# bitTree_2024-10-30.net
KiCad netlist of a schematic drawn in EasyEDA Pro
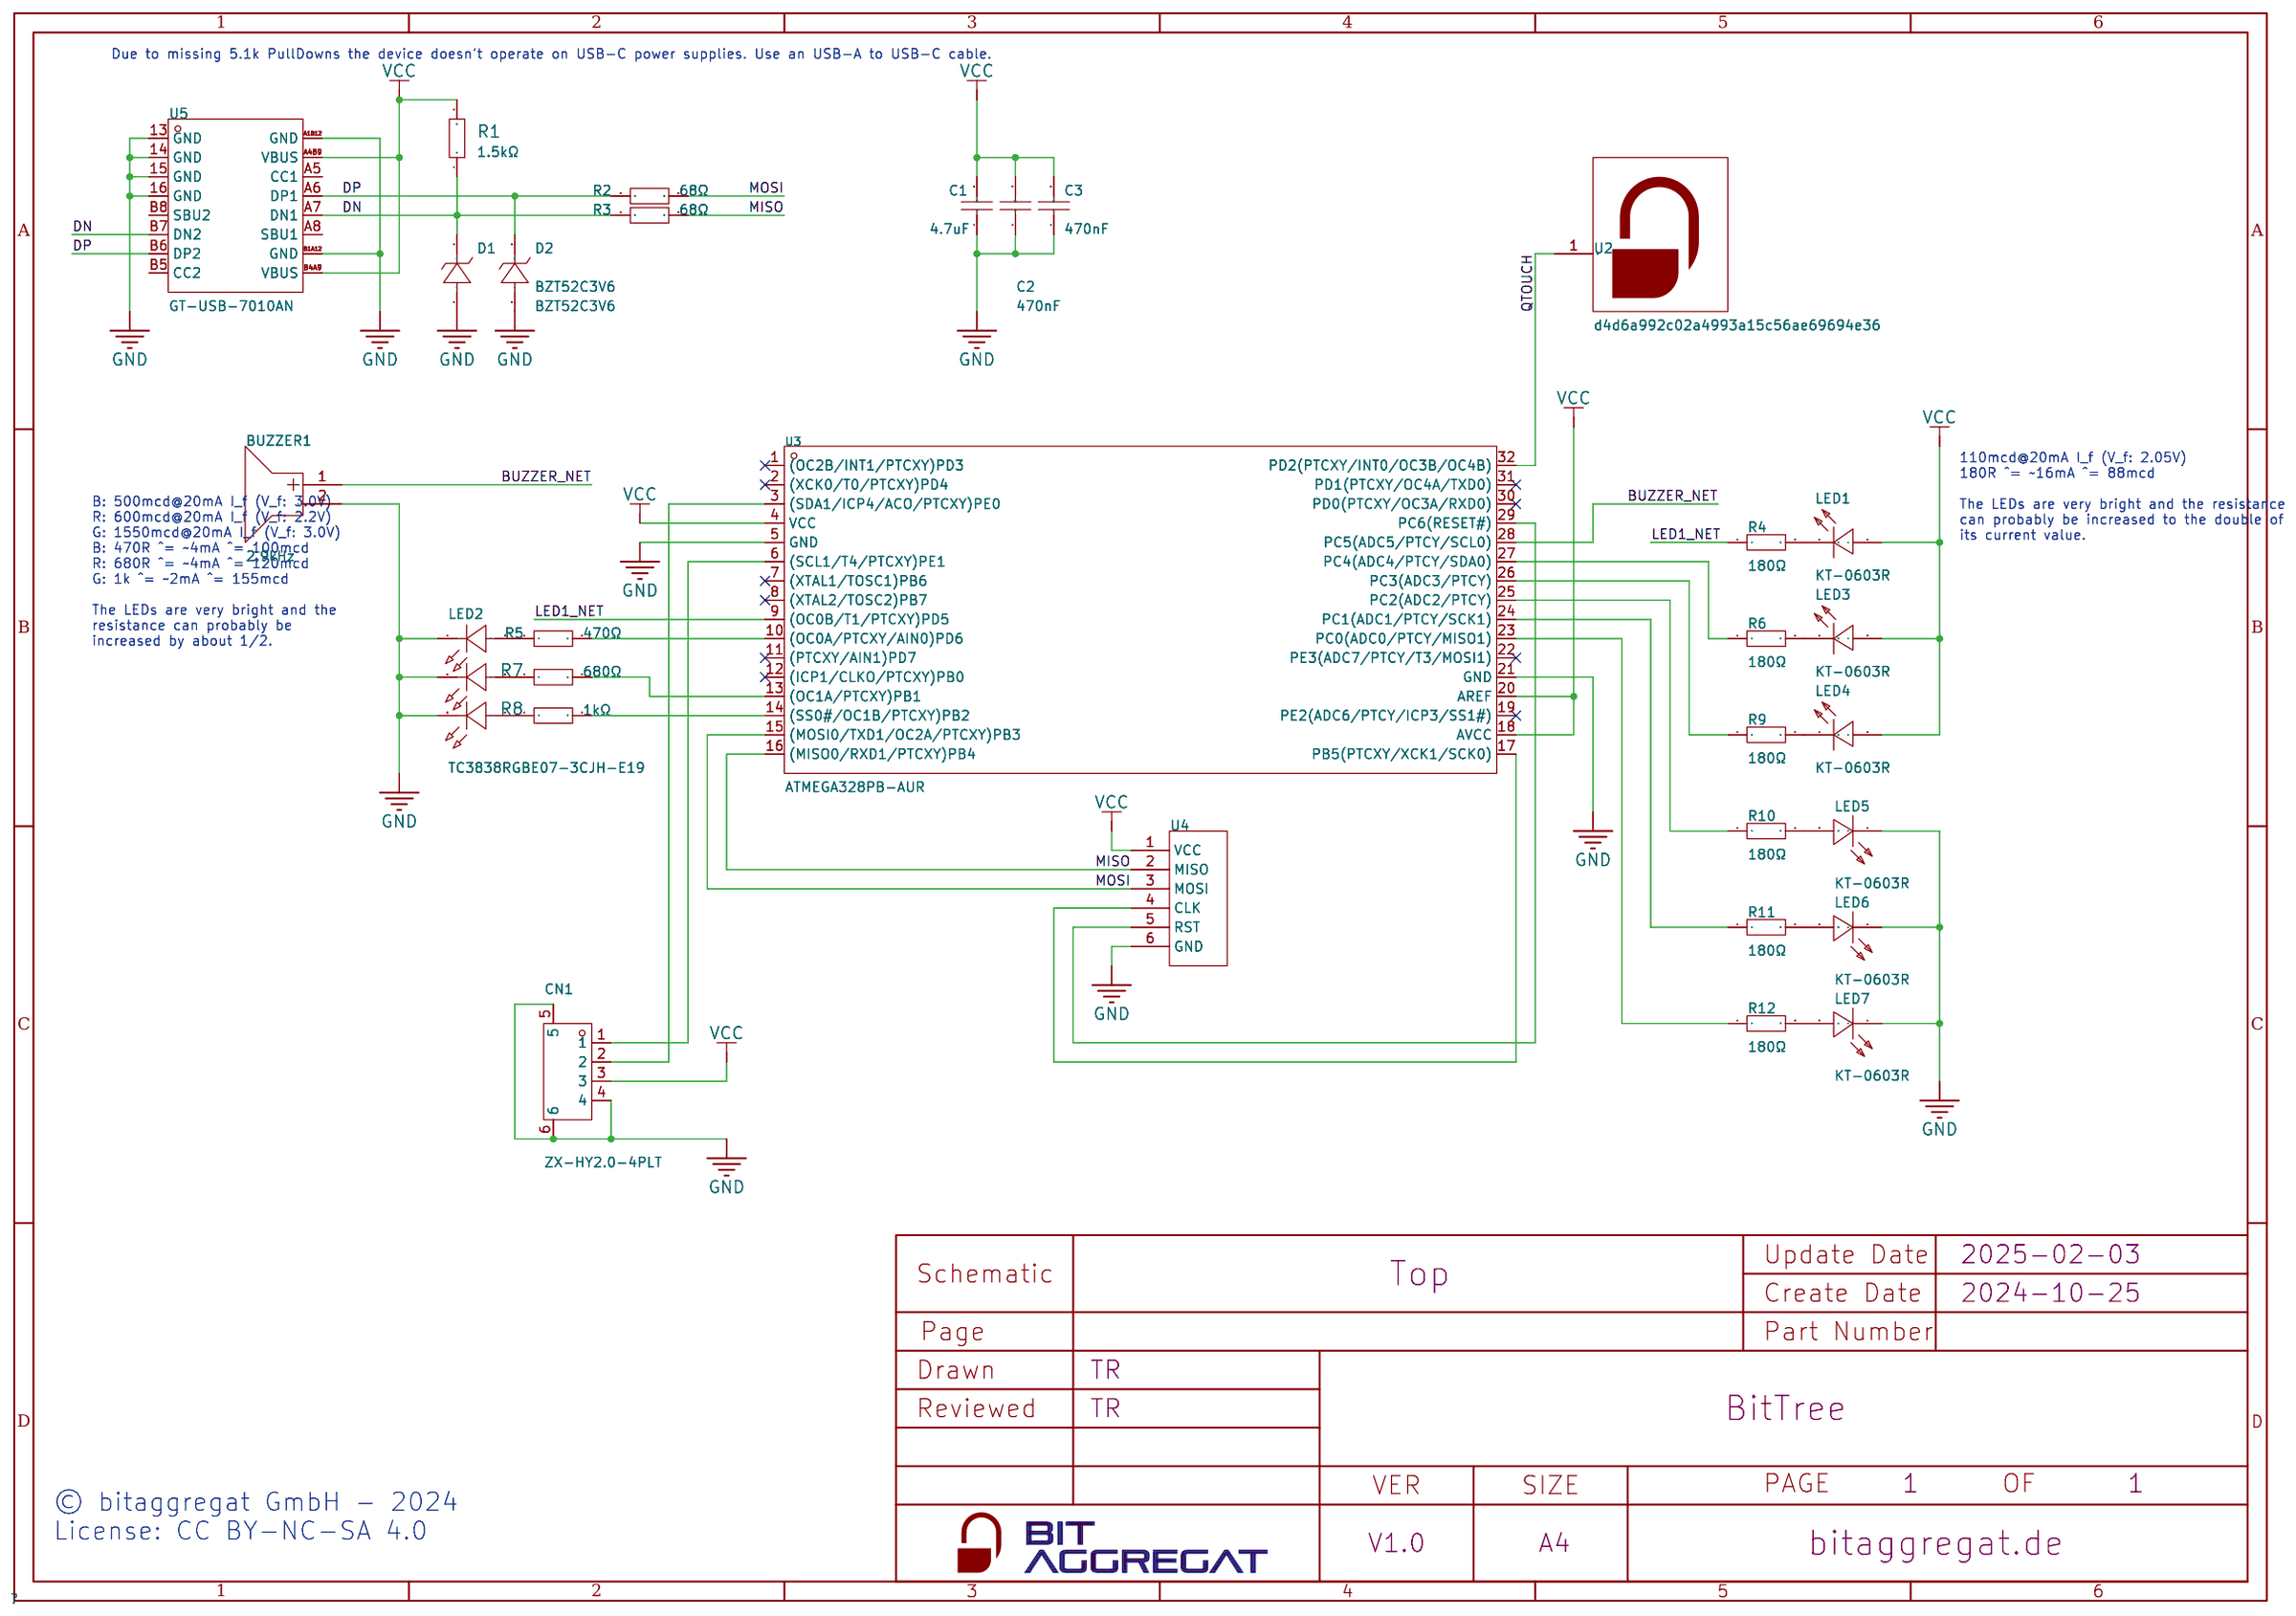
[diagram p0: schematic sheet]

(export (version "E")
  (design (tool "Eeschema 10.0.6"))
  (components
    (comp (ref "BUZZER1")
      (value "2.9kHz")
      (footprint "easyedapro:BUZ-TH_BD9.0-P5.00-D0.6-L-FD")
      (fields (field (name "Manufacturer Part") "Cy-9055-5029") (field (name "Manufacturer") "CY(超音)"))
      (libsource (lib "easyedapro") (part "CY-9055-5029"))
    )
    (comp (ref "C1")
      (value "4.7uF")
      (footprint "easyedapro:C0603")
      (fields
        (field (name "Manufacturer Part") "CL10A475KO8NNNC")
        (field (name "Manufacturer") "SAMSUNG(三星)")
      )
      (libsource (lib "easyedapro") (part "CL10A475KO8NNNC"))
    )
    (comp (ref "C2")
      (value "470nF")
      (footprint "easyedapro:C0603")
      (fields
        (field (name "Manufacturer Part") "CL10B474KA8NNNC")
        (field (name "Manufacturer") "SAMSUNG(三星)")
      )
      (libsource (lib "easyedapro") (part "CL10B474KA8NNNC"))
    )
    (comp (ref "C3")
      (value "470nF")
      (footprint "easyedapro:C0603")
      (fields
        (field (name "Manufacturer Part") "CL10B474KA8NNNC")
        (field (name "Manufacturer") "SAMSUNG(三星)")
      )
      (libsource (lib "easyedapro") (part "CL10B474KA8NNNC"))
    )
    (comp (ref "CN1")
      (value "ZX-HY2.0-4PLT")
      (footprint "easyedapro:CONN-SMD_4P-P2.00_HY2.0-4P")
      (fields (field (name "Manufacturer") "Megastar(兆星)"))
      (libsource (lib "easyedapro") (part "ZX-HY2.0-4PLT"))
    )
    (comp (ref "D1")
      (value "BZT52C3V6")
      (footprint "easyedapro:SOD-123_L2.7-W1.6-LS3.7-RD")
      (fields (field (name "Manufacturer") "宏迦橙"))
      (libsource (lib "easyedapro") (part "BZT52C3V6_C19077397"))
    )
    (comp (ref "D2")
      (value "BZT52C3V6")
      (footprint "easyedapro:SOD-123_L2.7-W1.6-LS3.7-RD")
      (fields (field (name "Manufacturer") "宏迦橙"))
      (libsource (lib "easyedapro") (part "BZT52C3V6_C19077397"))
    )
    (comp (ref "LED1")
      (value "KT-0603R")
      (footprint "easyedapro:LED0603-RD")
      (fields (field (name "Manufacturer") "KENTO"))
      (libsource (lib "easyedapro") (part "KT-0603R"))
    )
    (comp (ref "LED2")
      (value "TC3838RGBE07-3CJH-E19")
      (footprint "easyedapro:LED-SMD_6P-L3.5-W3.5-BL")
      (fields (field (name "Manufacturer") "TCWIN(天成)"))
      (libsource (lib "easyedapro") (part "TC3838RGBE07-3CJH-E19"))
    )
    (comp (ref "LED3")
      (value "KT-0603R")
      (footprint "easyedapro:LED0603-RD")
      (fields (field (name "Manufacturer") "KENTO"))
      (libsource (lib "easyedapro") (part "KT-0603R"))
    )
    (comp (ref "LED4")
      (value "KT-0603R")
      (footprint "easyedapro:LED0603-RD")
      (fields (field (name "Manufacturer") "KENTO"))
      (libsource (lib "easyedapro") (part "KT-0603R"))
    )
    (comp (ref "LED5")
      (value "KT-0603R")
      (footprint "easyedapro:LED0603-RD")
      (fields (field (name "Manufacturer") "KENTO"))
      (libsource (lib "easyedapro") (part "KT-0603R"))
    )
    (comp (ref "LED6")
      (value "KT-0603R")
      (footprint "easyedapro:LED0603-RD")
      (fields (field (name "Manufacturer") "KENTO"))
      (libsource (lib "easyedapro") (part "KT-0603R"))
    )
    (comp (ref "LED7")
      (value "KT-0603R")
      (footprint "easyedapro:LED0603-RD")
      (fields (field (name "Manufacturer") "KENTO"))
      (libsource (lib "easyedapro") (part "KT-0603R"))
    )
    (comp (ref "R1")
      (value "1.5kΩ")
      (footprint "easyedapro:R0603")
      (fields
        (field (name "Manufacturer Part") "0603WAF1501T5E")
        (field (name "Manufacturer") "UNI-ROYAL(厚声)")
      )
      (libsource (lib "easyedapro") (part "0603WAF1501T5E"))
    )
    (comp (ref "R2")
      (value "68Ω")
      (footprint "easyedapro:R0603")
      (fields
        (field (name "Manufacturer Part") "0603WAF680JT5E")
        (field (name "Manufacturer") "UNI-ROYAL(厚声)")
      )
      (libsource (lib "easyedapro") (part "0603WAF680JT5E"))
    )
    (comp (ref "R3")
      (value "68Ω")
      (footprint "easyedapro:R0603")
      (fields
        (field (name "Manufacturer Part") "0603WAF680JT5E")
        (field (name "Manufacturer") "UNI-ROYAL(厚声)")
      )
      (libsource (lib "easyedapro") (part "0603WAF680JT5E"))
    )
    (comp (ref "R4")
      (value "180Ω")
      (footprint "easyedapro:R0603")
      (fields
        (field (name "Manufacturer Part") "0603WAF1800T5E")
        (field (name "Manufacturer") "UNI-ROYAL(厚声)")
      )
      (libsource (lib "easyedapro") (part "0603WAF1800T5E"))
    )
    (comp (ref "R5")
      (value "470Ω")
      (footprint "easyedapro:R0603")
      (fields
        (field (name "Manufacturer Part") "0603WAF4700T5E")
        (field (name "Manufacturer") "UNI-ROYAL(厚声)")
      )
      (libsource (lib "easyedapro") (part "0603WAF4700T5E"))
    )
    (comp (ref "R6")
      (value "180Ω")
      (footprint "easyedapro:R0603")
      (fields
        (field (name "Manufacturer Part") "0603WAF1800T5E")
        (field (name "Manufacturer") "UNI-ROYAL(厚声)")
      )
      (libsource (lib "easyedapro") (part "0603WAF1800T5E"))
    )
    (comp (ref "R7")
      (value "680Ω")
      (footprint "easyedapro:R0603")
      (fields
        (field (name "Manufacturer Part") "0603WAF6800T5E")
        (field (name "Manufacturer") "UNI-ROYAL(厚声)")
      )
      (libsource (lib "easyedapro") (part "0603WAF6800T5E"))
    )
    (comp (ref "R8")
      (value "1kΩ")
      (footprint "easyedapro:R0603")
      (fields
        (field (name "Manufacturer Part") "0603WAF1001T5E")
        (field (name "Manufacturer") "UNI-ROYAL(厚声)")
      )
      (libsource (lib "easyedapro") (part "0603WAF1001T5E"))
    )
    (comp (ref "R9")
      (value "180Ω")
      (footprint "easyedapro:R0603")
      (fields
        (field (name "Manufacturer Part") "0603WAF1800T5E")
        (field (name "Manufacturer") "UNI-ROYAL(厚声)")
      )
      (libsource (lib "easyedapro") (part "0603WAF1800T5E"))
    )
    (comp (ref "R10")
      (value "180Ω")
      (footprint "easyedapro:R0603")
      (fields
        (field (name "Manufacturer Part") "0603WAF1800T5E")
        (field (name "Manufacturer") "UNI-ROYAL(厚声)")
      )
      (libsource (lib "easyedapro") (part "0603WAF1800T5E"))
    )
    (comp (ref "R11")
      (value "180Ω")
      (footprint "easyedapro:R0603")
      (fields
        (field (name "Manufacturer Part") "0603WAF1800T5E")
        (field (name "Manufacturer") "UNI-ROYAL(厚声)")
      )
      (libsource (lib "easyedapro") (part "0603WAF1800T5E"))
    )
    (comp (ref "R12")
      (value "180Ω")
      (footprint "easyedapro:R0603")
      (fields
        (field (name "Manufacturer Part") "0603WAF1800T5E")
        (field (name "Manufacturer") "UNI-ROYAL(厚声)")
      )
      (libsource (lib "easyedapro") (part "0603WAF1800T5E"))
    )
    (comp (ref "U2")
      (value "d4d6a992c02a4993a15c56ae69694e36")
      (footprint "easyedapro:QTouch-BA")
      (libsource (lib "easyedapro") (part "QTouch-BA"))
    )
    (comp (ref "U3")
      (value "ATMEGA328PB-AUR")
      (footprint "easyedapro:TQFP-32_L7.0-W7.0-P0.80-LS9.0-BL")
      (fields (field (name "Manufacturer") "MICROCHIP(美国微芯)"))
      (libsource (lib "easyedapro") (part "ATMEGA328PB-AUR"))
    )
    (comp (ref "U4")
      (value "~")
      (footprint "easyedapro:ProgrammingHeader")
      (libsource (lib "easyedapro") (part "ProgrammingHeader"))
    )
    (comp (ref "U5")
      (value "GT-USB-7010AN")
      (footprint "easyedapro:USB-SMD_GT-USB-7010AN")
      (fields (field (name "Manufacturer") "G-Switch(品赞)"))
      (libsource (lib "easyedapro") (part "GT-USB-7010AN"))
    )
  )
  (nets
    (net (code "1") (name "/BUZZER_NET") (class "Default")
      (node (ref "BUZZER1") (pin "1") (pinfunction "+_1") (pintype "input"))
      (node (ref "U3") (pin "28") (pinfunction "PC5(ADC5/PTCY/SCL0)_28") (pintype "input"))
    )
    (net (code "2") (name "/DN") (class "Default")
      (node (ref "D1") (pin "1") (pinfunction "K_1") (pintype "unspecified"))
      (node (ref "R1") (pin "1") (pinfunction "1_1") (pintype "input"))
      (node (ref "R3") (pin "1") (pinfunction "1_1") (pintype "input"))
      (node (ref "U5") (pin "A7") (pinfunction "DN1_A7") (pintype "unspecified"))
      (node (ref "U5") (pin "B7") (pinfunction "DN2_B7") (pintype "unspecified"))
    )
    (net (code "3") (name "/DP") (class "Default")
      (node (ref "D2") (pin "1") (pinfunction "K_1") (pintype "unspecified"))
      (node (ref "R2") (pin "1") (pinfunction "1_1") (pintype "input"))
      (node (ref "U5") (pin "A6") (pinfunction "DP1_A6") (pintype "unspecified"))
      (node (ref "U5") (pin "B6") (pinfunction "DP2_B6") (pintype "unspecified"))
    )
    (net (code "4") (name "/LED1_NET") (class "Default")
      (node (ref "R4") (pin "1") (pinfunction "1_1") (pintype "input"))
      (node (ref "U3") (pin "9") (pinfunction "(OC0B/T1/PTCXY)PD5_9") (pintype "input"))
    )
    (net (code "5") (name "/MISO") (class "Default")
      (node (ref "R3") (pin "2") (pinfunction "2_2") (pintype "input"))
      (node (ref "U3") (pin "16") (pinfunction "(MISO0/RXD1/PTCXY)PB4_16") (pintype "input"))
      (node (ref "U4") (pin "2") (pinfunction "MISO_2") (pintype "input"))
    )
    (net (code "6") (name "/MOSI") (class "Default")
      (node (ref "R2") (pin "2") (pinfunction "2_2") (pintype "input"))
      (node (ref "U3") (pin "15") (pinfunction "(MOSI0/TXD1/OC2A/PTCXY)PB3_15") (pintype "input"))
      (node (ref "U4") (pin "3") (pinfunction "MOSI_3") (pintype "input"))
    )
    (net (code "7") (name "/QTOUCH") (class "Default")
      (node (ref "U2") (pin "1") (pinfunction "1_1") (pintype "input"))
      (node (ref "U3") (pin "32") (pinfunction "PD2(PTCXY/INT0/OC3B/OC4B)_32") (pintype "input"))
    )
    (net (code "8") (name "GND") (class "Default")
      (node (ref "BUZZER1") (pin "2") (pinfunction "-_2") (pintype "input"))
      (node (ref "C1") (pin "1") (pinfunction "1_1") (pintype "input"))
      (node (ref "C2") (pin "1") (pinfunction "1_1") (pintype "input"))
      (node (ref "C3") (pin "1") (pinfunction "1_1") (pintype "input"))
      (node (ref "CN1") (pin "4") (pinfunction "4_4") (pintype "unspecified"))
      (node (ref "CN1") (pin "5") (pinfunction "5_5") (pintype "unspecified"))
      (node (ref "CN1") (pin "6") (pinfunction "6_6") (pintype "unspecified"))
      (node (ref "D1") (pin "2") (pinfunction "A_2") (pintype "unspecified"))
      (node (ref "D2") (pin "2") (pinfunction "A_2") (pintype "unspecified"))
      (node (ref "LED2") (pin "4") (pinfunction "-_4") (pintype "unspecified"))
      (node (ref "LED2") (pin "5") (pinfunction "-_5") (pintype "unspecified"))
      (node (ref "LED2") (pin "6") (pinfunction "-_6") (pintype "unspecified"))
      (node (ref "LED5") (pin "1") (pinfunction "K_1") (pintype "unspecified"))
      (node (ref "LED6") (pin "1") (pinfunction "K_1") (pintype "unspecified"))
      (node (ref "LED7") (pin "1") (pinfunction "K_1") (pintype "unspecified"))
      (node (ref "U3") (pin "21") (pinfunction "GND_21") (pintype "input"))
      (node (ref "U3") (pin "5") (pinfunction "GND_5") (pintype "input"))
      (node (ref "U4") (pin "6") (pinfunction "GND_6") (pintype "input"))
      (node (ref "U5") (pin "13") (pinfunction "GND_13") (pintype "unspecified"))
      (node (ref "U5") (pin "14") (pinfunction "GND_14") (pintype "unspecified"))
      (node (ref "U5") (pin "15") (pinfunction "GND_15") (pintype "unspecified"))
      (node (ref "U5") (pin "16") (pinfunction "GND_16") (pintype "unspecified"))
      (node (ref "U5") (pin "A1B12") (pinfunction "GND_A1B12") (pintype "unspecified"))
      (node (ref "U5") (pin "B1A12") (pinfunction "GND_B1A12") (pintype "unspecified"))
    )
    (net (code "9") (name "Net-(LED1-K)") (class "Default")
      (node (ref "LED1") (pin "1") (pinfunction "K_1") (pintype "unspecified"))
      (node (ref "R4") (pin "2") (pinfunction "2_2") (pintype "input"))
    )
    (net (code "10") (name "Net-(LED2-+-Pad1)") (class "Default")
      (node (ref "LED2") (pin "1") (pinfunction "+_1") (pintype "unspecified"))
      (node (ref "R8") (pin "1") (pinfunction "1_1") (pintype "input"))
    )
    (net (code "11") (name "Net-(LED2-+-Pad2)") (class "Default")
      (node (ref "LED2") (pin "2") (pinfunction "+_2") (pintype "unspecified"))
      (node (ref "R7") (pin "1") (pinfunction "1_1") (pintype "input"))
    )
    (net (code "12") (name "Net-(LED2-+-Pad3)") (class "Default")
      (node (ref "LED2") (pin "3") (pinfunction "+_3") (pintype "unspecified"))
      (node (ref "R5") (pin "1") (pinfunction "1_1") (pintype "input"))
    )
    (net (code "13") (name "Net-(LED3-K)") (class "Default")
      (node (ref "LED3") (pin "1") (pinfunction "K_1") (pintype "unspecified"))
      (node (ref "R6") (pin "2") (pinfunction "2_2") (pintype "input"))
    )
    (net (code "14") (name "Net-(LED4-K)") (class "Default")
      (node (ref "LED4") (pin "1") (pinfunction "K_1") (pintype "unspecified"))
      (node (ref "R9") (pin "2") (pinfunction "2_2") (pintype "input"))
    )
    (net (code "15") (name "Net-(LED5-A)") (class "Default")
      (node (ref "LED5") (pin "2") (pinfunction "A_2") (pintype "unspecified"))
      (node (ref "R10") (pin "2") (pinfunction "2_2") (pintype "input"))
    )
    (net (code "16") (name "Net-(LED6-A)") (class "Default")
      (node (ref "LED6") (pin "2") (pinfunction "A_2") (pintype "unspecified"))
      (node (ref "R11") (pin "2") (pinfunction "2_2") (pintype "input"))
    )
    (net (code "17") (name "Net-(LED7-A)") (class "Default")
      (node (ref "LED7") (pin "2") (pinfunction "A_2") (pintype "unspecified"))
      (node (ref "R12") (pin "2") (pinfunction "2_2") (pintype "input"))
    )
    (net (code "18") (name "Net-(U3-(OC0A{slash}PTCXY{slash}AIN0)PD6)") (class "Default")
      (node (ref "R5") (pin "2") (pinfunction "2_2") (pintype "input"))
      (node (ref "U3") (pin "10") (pinfunction "(OC0A/PTCXY/AIN0)PD6_10") (pintype "input"))
    )
    (net (code "19") (name "Net-(U3-(OC1A{slash}PTCXY)PB1)") (class "Default")
      (node (ref "R7") (pin "2") (pinfunction "2_2") (pintype "input"))
      (node (ref "U3") (pin "13") (pinfunction "(OC1A/PTCXY)PB1_13") (pintype "input"))
    )
    (net (code "20") (name "Net-(U3-(SCL1{slash}T4{slash}PTCXY)PE1)") (class "Default")
      (node (ref "CN1") (pin "1") (pinfunction "1_1") (pintype "unspecified"))
      (node (ref "U3") (pin "6") (pinfunction "(SCL1/T4/PTCXY)PE1_6") (pintype "input"))
    )
    (net (code "21") (name "Net-(U3-(SDA1{slash}ICP4{slash}ACO{slash}PTCXY)PE0)") (class "Default")
      (node (ref "CN1") (pin "2") (pinfunction "2_2") (pintype "unspecified"))
      (node (ref "U3") (pin "3") (pinfunction "(SDA1/ICP4/ACO/PTCXY)PE0_3") (pintype "input"))
    )
    (net (code "22") (name "Net-(U3-(SS0#{slash}OC1B{slash}PTCXY)PB2)") (class "Default")
      (node (ref "R8") (pin "2") (pinfunction "2_2") (pintype "input"))
      (node (ref "U3") (pin "14") (pinfunction "(SS0#/OC1B/PTCXY)PB2_14") (pintype "input"))
    )
    (net (code "23") (name "Net-(U3-PB5(PTCXY{slash}XCK1{slash}SCK0))") (class "Default")
      (node (ref "U3") (pin "17") (pinfunction "PB5(PTCXY/XCK1/SCK0)_17") (pintype "input"))
      (node (ref "U4") (pin "4") (pinfunction "CLK_4") (pintype "input"))
    )
    (net (code "24") (name "Net-(U3-PC0(ADC0{slash}PTCY{slash}MISO1))") (class "Default")
      (node (ref "R12") (pin "1") (pinfunction "1_1") (pintype "input"))
      (node (ref "U3") (pin "23") (pinfunction "PC0(ADC0/PTCY/MISO1)_23") (pintype "input"))
    )
    (net (code "25") (name "Net-(U3-PC1(ADC1{slash}PTCY{slash}SCK1))") (class "Default")
      (node (ref "R11") (pin "1") (pinfunction "1_1") (pintype "input"))
      (node (ref "U3") (pin "24") (pinfunction "PC1(ADC1/PTCY/SCK1)_24") (pintype "input"))
    )
    (net (code "26") (name "Net-(U3-PC2(ADC2{slash}PTCY))") (class "Default")
      (node (ref "R10") (pin "1") (pinfunction "1_1") (pintype "input"))
      (node (ref "U3") (pin "25") (pinfunction "PC2(ADC2/PTCY)_25") (pintype "input"))
    )
    (net (code "27") (name "Net-(U3-PC3(ADC3{slash}PTCY))") (class "Default")
      (node (ref "R9") (pin "1") (pinfunction "1_1") (pintype "input"))
      (node (ref "U3") (pin "26") (pinfunction "PC3(ADC3/PTCY)_26") (pintype "input"))
    )
    (net (code "28") (name "Net-(U3-PC4(ADC4{slash}PTCY{slash}SDA0))") (class "Default")
      (node (ref "R6") (pin "1") (pinfunction "1_1") (pintype "input"))
      (node (ref "U3") (pin "27") (pinfunction "PC4(ADC4/PTCY/SDA0)_27") (pintype "input"))
    )
    (net (code "29") (name "Net-(U3-PC6(RESET#))") (class "Default")
      (node (ref "U3") (pin "29") (pinfunction "PC6(RESET#)_29") (pintype "input"))
      (node (ref "U4") (pin "5") (pinfunction "RST_5") (pintype "input"))
    )
    (net (code "30") (name "VCC") (class "Default")
      (node (ref "C1") (pin "2") (pinfunction "2_2") (pintype "input"))
      (node (ref "C2") (pin "2") (pinfunction "2_2") (pintype "input"))
      (node (ref "C3") (pin "2") (pinfunction "2_2") (pintype "input"))
      (node (ref "CN1") (pin "3") (pinfunction "3_3") (pintype "unspecified"))
      (node (ref "LED1") (pin "2") (pinfunction "A_2") (pintype "unspecified"))
      (node (ref "LED3") (pin "2") (pinfunction "A_2") (pintype "unspecified"))
      (node (ref "LED4") (pin "2") (pinfunction "A_2") (pintype "unspecified"))
      (node (ref "R1") (pin "2") (pinfunction "2_2") (pintype "input"))
      (node (ref "U3") (pin "18") (pinfunction "AVCC_18") (pintype "input"))
      (node (ref "U3") (pin "20") (pinfunction "AREF_20") (pintype "input"))
      (node (ref "U3") (pin "4") (pinfunction "VCC_4") (pintype "input"))
      (node (ref "U4") (pin "1") (pinfunction "VCC_1") (pintype "input"))
      (node (ref "U5") (pin "A4B9") (pinfunction "VBUS_A4B9") (pintype "unspecified"))
      (node (ref "U5") (pin "B4A9") (pinfunction "VBUS_B4A9") (pintype "unspecified"))
    )
    (net (code "31") (name "unconnected-(U3-(ICP1{slash}CLKO{slash}PTCXY)PB0-Pad12)") (class "Default")
      (node (ref "U3") (pin "12") (pinfunction "(ICP1/CLKO/PTCXY)PB0_12") (pintype "input+no_connect"))
    )
    (net (code "32") (name "unconnected-(U3-(OC2B{slash}INT1{slash}PTCXY)PD3-Pad1)") (class "Default")
      (node (ref "U3") (pin "1") (pinfunction "(OC2B/INT1/PTCXY)PD3_1") (pintype "input+no_connect"))
    )
    (net (code "33") (name "unconnected-(U3-(PTCXY{slash}AIN1)PD7-Pad11)") (class "Default")
      (node (ref "U3") (pin "11") (pinfunction "(PTCXY/AIN1)PD7_11") (pintype "input+no_connect"))
    )
    (net (code "34") (name "unconnected-(U3-(XCK0{slash}T0{slash}PTCXY)PD4-Pad2)") (class "Default")
      (node (ref "U3") (pin "2") (pinfunction "(XCK0/T0/PTCXY)PD4_2") (pintype "input+no_connect"))
    )
    (net (code "35") (name "unconnected-(U3-(XTAL1{slash}TOSC1)PB6-Pad7)") (class "Default")
      (node (ref "U3") (pin "7") (pinfunction "(XTAL1/TOSC1)PB6_7") (pintype "input+no_connect"))
    )
    (net (code "36") (name "unconnected-(U3-(XTAL2{slash}TOSC2)PB7-Pad8)") (class "Default")
      (node (ref "U3") (pin "8") (pinfunction "(XTAL2/TOSC2)PB7_8") (pintype "input+no_connect"))
    )
    (net (code "37") (name "unconnected-(U3-PD0(PTCXY{slash}OC3A{slash}RXD0)-Pad30)") (class "Default")
      (node (ref "U3") (pin "30") (pinfunction "PD0(PTCXY/OC3A/RXD0)_30") (pintype "input+no_connect"))
    )
    (net (code "38") (name "unconnected-(U3-PD1(PTCXY{slash}OC4A{slash}TXD0)-Pad31)") (class "Default")
      (node (ref "U3") (pin "31") (pinfunction "PD1(PTCXY/OC4A/TXD0)_31") (pintype "input+no_connect"))
    )
    (net (code "39") (name "unconnected-(U3-PE2(ADC6{slash}PTCY{slash}ICP3{slash}SS1#)-Pad19)") (class "Default")
      (node (ref "U3") (pin "19") (pinfunction "PE2(ADC6/PTCY/ICP3/SS1#)_19") (pintype "input+no_connect"))
    )
    (net (code "40") (name "unconnected-(U3-PE3(ADC7{slash}PTCY{slash}T3{slash}MOSI1)-Pad22)") (class "Default")
      (node (ref "U3") (pin "22") (pinfunction "PE3(ADC7/PTCY/T3/MOSI1)_22") (pintype "input+no_connect"))
    )
    (net (code "41") (name "unconnected-(U5-CC1-PadA5)") (class "Default")
      (node (ref "U5") (pin "A5") (pinfunction "CC1_A5") (pintype "unspecified"))
    )
    (net (code "42") (name "unconnected-(U5-CC2-PadB5)") (class "Default")
      (node (ref "U5") (pin "B5") (pinfunction "CC2_B5") (pintype "unspecified"))
    )
    (net (code "43") (name "unconnected-(U5-SBU1-PadA8)") (class "Default")
      (node (ref "U5") (pin "A8") (pinfunction "SBU1_A8") (pintype "unspecified"))
    )
    (net (code "44") (name "unconnected-(U5-SBU2-PadB8)") (class "Default")
      (node (ref "U5") (pin "B8") (pinfunction "SBU2_B8") (pintype "unspecified"))
    )
  )
)
